# LilyPad-Dev-Simple-v12.net
KiCad netlist of a schematic drawn in EAGLE
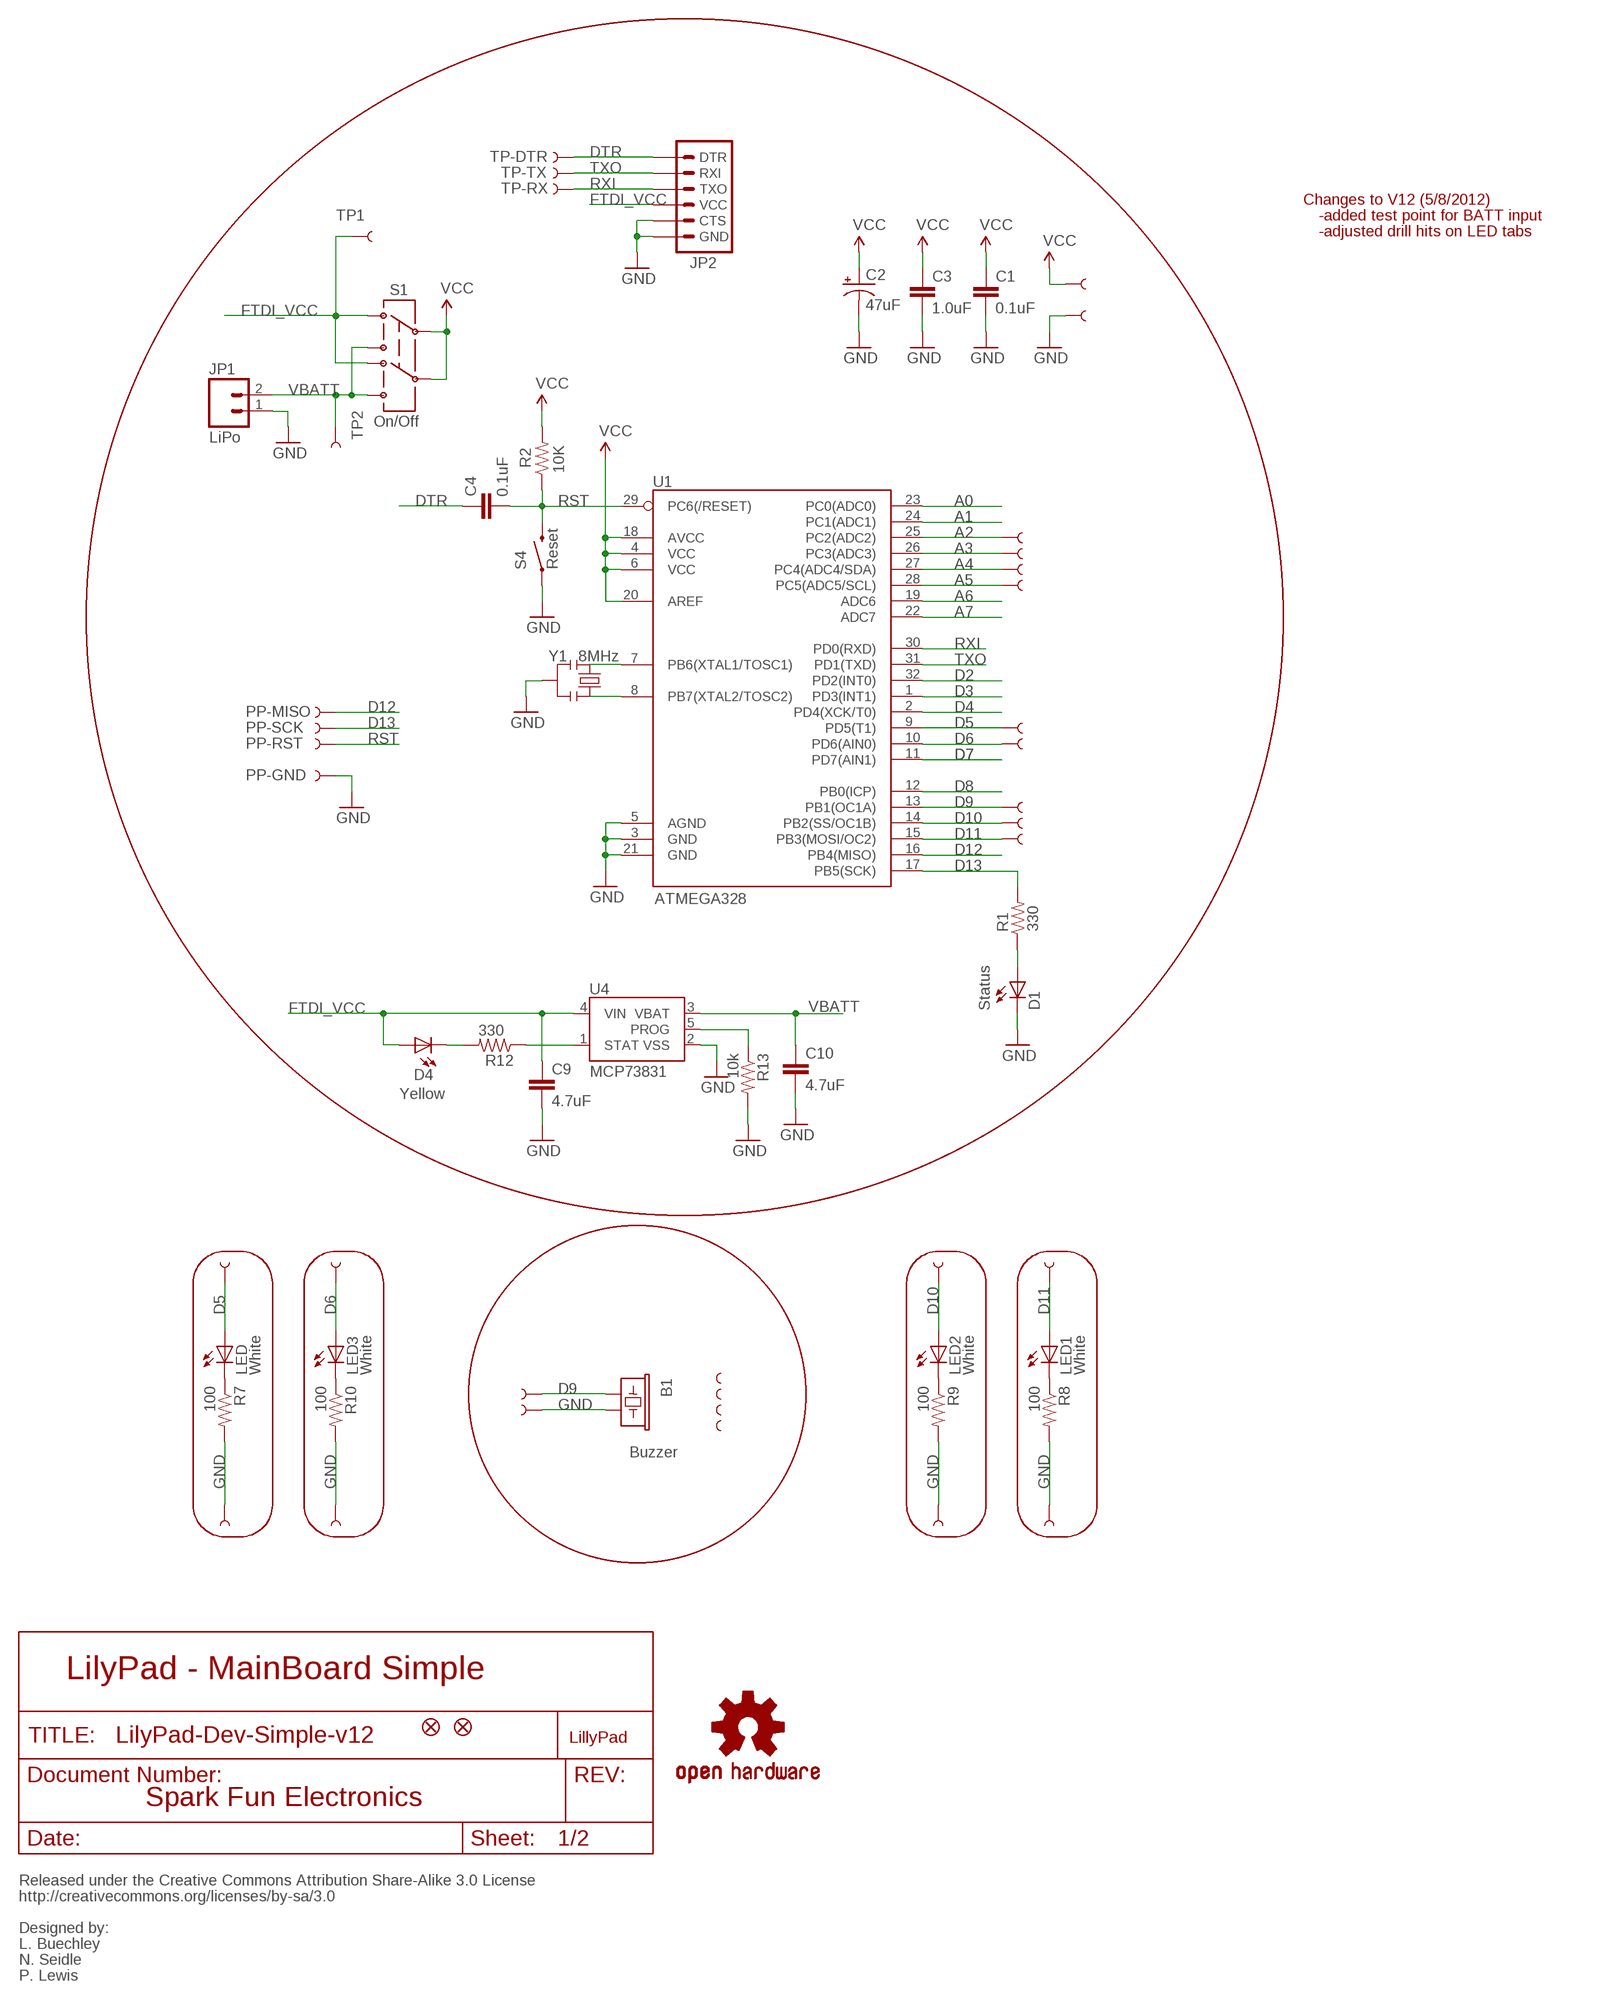
[diagram p0: schematic, sheet 1]

(export (version "E")
  (design (tool "Eeschema 10.0.6"))
  (components
    (comp (ref "1")
      (value "SEWTAP-NOHOLE2")
      (footprint "eagle-import:PETAL-NOHOLE-2SIDE")
      (libsource (lib "eagle-import") (part "SEWTAP-NOHOLE2"))
    )
    (comp (ref "2")
      (value "SEWTAP-NOHOLE2")
      (footprint "eagle-import:PETAL-NOHOLE-2SIDE")
      (libsource (lib "eagle-import") (part "SEWTAP-NOHOLE2"))
    )
    (comp (ref "3")
      (value "SEWTAP-NOHOLE2")
      (footprint "eagle-import:PETAL-NOHOLE-2SIDE")
      (libsource (lib "eagle-import") (part "SEWTAP-NOHOLE2"))
    )
    (comp (ref "4")
      (value "SEWTAP-NOHOLE2")
      (footprint "eagle-import:PETAL-NOHOLE-2SIDE")
      (libsource (lib "eagle-import") (part "SEWTAP-NOHOLE2"))
    )
    (comp (ref "A2/16")
      (value "SEWTAP9")
      (footprint "eagle-import:PETAL-LONG-1-2SIDE")
      (libsource (lib "eagle-import") (part "SEWTAP9"))
    )
    (comp (ref "A3/17")
      (value "SEWTAP9")
      (footprint "eagle-import:PETAL-LONG-1-2SIDE")
      (libsource (lib "eagle-import") (part "SEWTAP9"))
    )
    (comp (ref "A4/18")
      (value "SEWTAP9")
      (footprint "eagle-import:PETAL-LONG-1-2SIDE")
      (libsource (lib "eagle-import") (part "SEWTAP9"))
    )
    (comp (ref "A5/19")
      (value "SEWTAP9")
      (footprint "eagle-import:PETAL-LONG-1-2SIDE")
      (libsource (lib "eagle-import") (part "SEWTAP9"))
    )
    (comp (ref "B1")
      (value "Buzzer")
      (footprint "eagle-import:BUZZER-CCV")
      (libsource (lib "eagle-import") (part "BUZZERSMD2"))
    )
    (comp (ref "C1")
      (value "0.1uF")
      (footprint "eagle-import:0402-CAP")
      (libsource (lib "eagle-import") (part "CAP0402-CAP"))
    )
    (comp (ref "C2")
      (value "47uF")
      (footprint "eagle-import:EIA3528")
      (libsource (lib "eagle-import") (part "CAP_POL3528"))
    )
    (comp (ref "C3")
      (value "1.0uF")
      (footprint "eagle-import:0402-CAP")
      (libsource (lib "eagle-import") (part "CAP0402-CAP"))
    )
    (comp (ref "C4")
      (value "0.1uF")
      (footprint "eagle-import:0402-CAP")
      (libsource (lib "eagle-import") (part "CAP0402-CAP"))
    )
    (comp (ref "C9")
      (value "4.7uF")
      (footprint "eagle-import:0402-CAP")
      (libsource (lib "eagle-import") (part "CAP0402-CAP"))
    )
    (comp (ref "C10")
      (value "4.7uF")
      (footprint "eagle-import:0402-CAP")
      (libsource (lib "eagle-import") (part "CAP0402-CAP"))
    )
    (comp (ref "D1")
      (value "Status")
      (footprint "eagle-import:LED-0603")
      (libsource (lib "eagle-import") (part "LED0603"))
    )
    (comp (ref "D4")
      (value "Yellow")
      (footprint "eagle-import:LED-0603")
      (libsource (lib "eagle-import") (part "LED0603"))
    )
    (comp (ref "JP1")
      (value "LiPo")
      (footprint "eagle-import:JST-2-SMD")
      (libsource (lib "eagle-import") (part "M02-JST-2MM-SMT"))
    )
    (comp (ref "JP2")
      (value "ARDUINO_SERIAL_PROGRAMSMD")
      (footprint "eagle-import:1X06-SMD")
      (libsource (lib "eagle-import") (part "ARDUINO_SERIAL_PROGRAMSMD"))
    )
    (comp (ref "JP3")
      (value "FIDUCIAL1X2")
      (footprint "eagle-import:FIDUCIAL-1X2")
      (libsource (lib "eagle-import") (part "FIDUCIAL1X2"))
    )
    (comp (ref "JP4")
      (value "FIDUCIAL1X2")
      (footprint "eagle-import:FIDUCIAL-1X2")
      (libsource (lib "eagle-import") (part "FIDUCIAL1X2"))
    )
    (comp (ref "LED")
      (value "White")
      (footprint "eagle-import:LED-1206")
      (libsource (lib "eagle-import") (part "SparkFun-3-2-07_LED1206"))
    )
    (comp (ref "LED+")
      (value "SEWTAP6")
      (footprint "eagle-import:PETAL-SMALL-2SIDE")
      (libsource (lib "eagle-import") (part "SEWTAP6"))
    )
    (comp (ref "LED+1")
      (value "SEWTAP6")
      (footprint "eagle-import:PETAL-SMALL-2SIDE")
      (libsource (lib "eagle-import") (part "SEWTAP6"))
    )
    (comp (ref "LED+2")
      (value "SEWTAP6")
      (footprint "eagle-import:PETAL-SMALL-2SIDE")
      (libsource (lib "eagle-import") (part "SEWTAP6"))
    )
    (comp (ref "LED+3")
      (value "SEWTAP6")
      (footprint "eagle-import:PETAL-SMALL-2SIDE")
      (libsource (lib "eagle-import") (part "SEWTAP6"))
    )
    (comp (ref "LED-")
      (value "SEWTAP6")
      (footprint "eagle-import:PETAL-SMALL-2SIDE")
      (libsource (lib "eagle-import") (part "SEWTAP6"))
    )
    (comp (ref "LED-1")
      (value "SEWTAP6")
      (footprint "eagle-import:PETAL-SMALL-2SIDE")
      (libsource (lib "eagle-import") (part "SEWTAP6"))
    )
    (comp (ref "LED-2")
      (value "SEWTAP6")
      (footprint "eagle-import:PETAL-SMALL-2SIDE")
      (libsource (lib "eagle-import") (part "SEWTAP6"))
    )
    (comp (ref "LED-3")
      (value "SEWTAP6")
      (footprint "eagle-import:PETAL-SMALL-2SIDE")
      (libsource (lib "eagle-import") (part "SEWTAP6"))
    )
    (comp (ref "LED1")
      (value "White")
      (footprint "eagle-import:LED-1206")
      (libsource (lib "eagle-import") (part "SparkFun-3-2-07_LED1206"))
    )
    (comp (ref "LED2")
      (value "White")
      (footprint "eagle-import:LED-1206")
      (libsource (lib "eagle-import") (part "SparkFun-3-2-07_LED1206"))
    )
    (comp (ref "LED3")
      (value "White")
      (footprint "eagle-import:LED-1206")
      (libsource (lib "eagle-import") (part "SparkFun-3-2-07_LED1206"))
    )
    (comp (ref "LOGO")
      (value "LOGO-LPLPA")
      (footprint "eagle-import:LOGO-LPA")
      (libsource (lib "eagle-import") (part "LOGO-LPLPA"))
    )
    (comp (ref "PP-GND")
      (value "TEST-POINT3X5")
      (footprint "eagle-import:PAD.03X.05")
      (libsource (lib "eagle-import") (part "TEST-POINT3X5"))
    )
    (comp (ref "PP-MISO")
      (value "TEST-POINT3X5")
      (footprint "eagle-import:PAD.03X.05")
      (libsource (lib "eagle-import") (part "TEST-POINT3X5"))
    )
    (comp (ref "PP-RST")
      (value "TEST-POINT3X5")
      (footprint "eagle-import:PAD.03X.05")
      (libsource (lib "eagle-import") (part "TEST-POINT3X5"))
    )
    (comp (ref "PP-SCK")
      (value "TEST-POINT3X5")
      (footprint "eagle-import:PAD.03X.05")
      (libsource (lib "eagle-import") (part "TEST-POINT3X5"))
    )
    (comp (ref "R1")
      (value "330")
      (footprint "eagle-import:0402-RES")
      (libsource (lib "eagle-import") (part "RESISTOR0402-RES"))
    )
    (comp (ref "R2")
      (value "10K")
      (footprint "eagle-import:0402-RES")
      (libsource (lib "eagle-import") (part "RESISTOR0402-RES"))
    )
    (comp (ref "R7")
      (value "100")
      (footprint "eagle-import:0603-RES")
      (libsource (lib "eagle-import") (part "RESISTOR0603-RES"))
    )
    (comp (ref "R8")
      (value "100")
      (footprint "eagle-import:0603-RES")
      (libsource (lib "eagle-import") (part "RESISTOR0603-RES"))
    )
    (comp (ref "R9")
      (value "100")
      (footprint "eagle-import:0603-RES")
      (libsource (lib "eagle-import") (part "RESISTOR0603-RES"))
    )
    (comp (ref "R10")
      (value "100")
      (footprint "eagle-import:0603-RES")
      (libsource (lib "eagle-import") (part "RESISTOR0603-RES"))
    )
    (comp (ref "R12")
      (value "330")
      (footprint "eagle-import:0402-RES")
      (libsource (lib "eagle-import") (part "RESISTOR0402-RES"))
    )
    (comp (ref "R13")
      (value "10k")
      (footprint "eagle-import:0402-RES")
      (libsource (lib "eagle-import") (part "RESISTOR0402-RES"))
    )
    (comp (ref "S1")
      (value "On/Off")
      (footprint "eagle-import:AYZ0202")
      (libsource (lib "eagle-import") (part "AYZ0202"))
    )
    (comp (ref "S4")
      (value "Reset")
      (footprint "eagle-import:TACTILE_SWITCH_SMD")
      (libsource (lib "eagle-import") (part "SWITCH-MOMENTARY-2SMD"))
    )
    (comp (ref "TP-DTR")
      (value "TEST-POINT3X5")
      (footprint "eagle-import:PAD.03X.05")
      (libsource (lib "eagle-import") (part "TEST-POINT3X5"))
    )
    (comp (ref "TP-RX")
      (value "TEST-POINT3X5")
      (footprint "eagle-import:PAD.03X.05")
      (libsource (lib "eagle-import") (part "TEST-POINT3X5"))
    )
    (comp (ref "TP-TX")
      (value "TEST-POINT3X5")
      (footprint "eagle-import:PAD.03X.05")
      (libsource (lib "eagle-import") (part "TEST-POINT3X5"))
    )
    (comp (ref "TP1")
      (value "TEST-POINT3X5")
      (footprint "eagle-import:PAD.03X.05")
      (libsource (lib "eagle-import") (part "TEST-POINT3X5"))
    )
    (comp (ref "TP2")
      (value "TEST-POINT3X5")
      (footprint "eagle-import:PAD.03X.05")
      (libsource (lib "eagle-import") (part "TEST-POINT3X5"))
    )
    (comp (ref "U$1")
      (value "SEWTAP9")
      (footprint "eagle-import:PETAL-LONG-1-2SIDE")
      (libsource (lib "eagle-import") (part "SEWTAP9"))
    )
    (comp (ref "U$2")
      (value "OSHW-LOGOS")
      (footprint "eagle-import:OSHW-LOGO-S")
      (libsource (lib "eagle-import") (part "OSHW-LOGOS"))
    )
    (comp (ref "U$4")
      (value "SEWTAP9")
      (footprint "eagle-import:PETAL-LONG-1-2SIDE")
      (libsource (lib "eagle-import") (part "SEWTAP9"))
    )
    (comp (ref "U$32-")
      (value "SEWTAP6")
      (footprint "eagle-import:PETAL-SMALL")
      (libsource (lib "eagle-import") (part "SEWTAP4"))
    )
    (comp (ref "U$33+")
      (value "SEWTAP6")
      (footprint "eagle-import:PETAL-SMALL")
      (libsource (lib "eagle-import") (part "SEWTAP4"))
    )
    (comp (ref "U$37")
      (value "SEWTAP9")
      (footprint "eagle-import:PETAL-LONG-1-2SIDE")
      (libsource (lib "eagle-import") (part "SEWTAP9"))
    )
    (comp (ref "U$39")
      (value "SEWTAP9")
      (footprint "eagle-import:PETAL-LONG-1-2SIDE")
      (libsource (lib "eagle-import") (part "SEWTAP9"))
    )
    (comp (ref "U$41")
      (value "SEWTAP9")
      (footprint "eagle-import:PETAL-LONG-1-2SIDE")
      (libsource (lib "eagle-import") (part "SEWTAP9"))
    )
    (comp (ref "U$43")
      (value "SEWTAP9")
      (footprint "eagle-import:PETAL-LONG-1-2SIDE")
      (libsource (lib "eagle-import") (part "SEWTAP9"))
    )
    (comp (ref "U$45")
      (value "SEWTAP9")
      (footprint "eagle-import:PETAL-LONG-1-2SIDE")
      (libsource (lib "eagle-import") (part "SEWTAP9"))
    )
    (comp (ref "U1")
      (value "ATMEGA328")
      (footprint "eagle-import:TQFP32-08")
      (libsource (lib "eagle-import") (part "ATMEGA168"))
    )
    (comp (ref "U4")
      (value "MCP73831")
      (footprint "eagle-import:SOT23-5")
      (libsource (lib "eagle-import") (part "MCP73831"))
    )
    (comp (ref "Y1")
      (value "8MHz")
      (footprint "eagle-import:RESONATOR-SMD")
      (libsource (lib "eagle-import") (part "RESONATORSMD"))
    )
  )
  (nets
    (net (code "1") (name "A0") (class "Default")
      (node (ref "U1") (pin "23") (pinfunction "PC0(ADC0)_23") (pintype "bidirectional"))
    )
    (net (code "2") (name "A1") (class "Default")
      (node (ref "U1") (pin "24") (pinfunction "PC1(ADC1)_24") (pintype "bidirectional"))
    )
    (net (code "3") (name "A2") (class "Default")
      (node (ref "A2/16") (pin "1") (pinfunction "1_1") (pintype "bidirectional"))
      (node (ref "U1") (pin "25") (pinfunction "PC2(ADC2)_25") (pintype "bidirectional"))
    )
    (net (code "4") (name "A3") (class "Default")
      (node (ref "A3/17") (pin "1") (pinfunction "1_1") (pintype "bidirectional"))
      (node (ref "U1") (pin "26") (pinfunction "PC3(ADC3)_26") (pintype "bidirectional"))
    )
    (net (code "5") (name "A4") (class "Default")
      (node (ref "A4/18") (pin "1") (pinfunction "1_1") (pintype "bidirectional"))
      (node (ref "U1") (pin "27") (pinfunction "PC4(ADC4/SDA)_27") (pintype "bidirectional"))
    )
    (net (code "6") (name "A5") (class "Default")
      (node (ref "A5/19") (pin "1") (pinfunction "1_1") (pintype "bidirectional"))
      (node (ref "U1") (pin "28") (pinfunction "PC5(ADC5/SCL)_28") (pintype "bidirectional"))
    )
    (net (code "7") (name "A6") (class "Default")
      (node (ref "U1") (pin "19") (pinfunction "ADC6_19") (pintype "bidirectional"))
    )
    (net (code "8") (name "A7") (class "Default")
      (node (ref "U1") (pin "22") (pinfunction "ADC7_22") (pintype "bidirectional"))
    )
    (net (code "9") (name "D2") (class "Default")
      (node (ref "U1") (pin "32") (pinfunction "PD2(INT0)_32") (pintype "bidirectional"))
    )
    (net (code "10") (name "D3") (class "Default")
      (node (ref "U1") (pin "1") (pinfunction "PD3(INT1)_1") (pintype "bidirectional"))
    )
    (net (code "11") (name "D4") (class "Default")
      (node (ref "U1") (pin "2") (pinfunction "PD4(XCK/T0)_2") (pintype "bidirectional"))
    )
    (net (code "12") (name "D5") (class "Default")
      (node (ref "LED") (pin "A") (pinfunction "A_A") (pintype "passive"))
      (node (ref "LED+") (pin "1") (pinfunction "1_1") (pintype "bidirectional"))
      (node (ref "U$41") (pin "1") (pinfunction "1_1") (pintype "bidirectional"))
      (node (ref "U1") (pin "9") (pinfunction "PD5(T1)_9") (pintype "bidirectional"))
    )
    (net (code "13") (name "D6") (class "Default")
      (node (ref "LED+3") (pin "1") (pinfunction "1_1") (pintype "bidirectional"))
      (node (ref "LED3") (pin "A") (pinfunction "A_A") (pintype "passive"))
      (node (ref "U$1") (pin "1") (pinfunction "1_1") (pintype "bidirectional"))
      (node (ref "U1") (pin "10") (pinfunction "PD6(AIN0)_10") (pintype "bidirectional"))
    )
    (net (code "14") (name "D7") (class "Default")
      (node (ref "U1") (pin "11") (pinfunction "PD7(AIN1)_11") (pintype "bidirectional"))
    )
    (net (code "15") (name "D8") (class "Default")
      (node (ref "U1") (pin "12") (pinfunction "PB0(ICP)_12") (pintype "bidirectional"))
    )
    (net (code "16") (name "D9") (class "Default")
      (node (ref "B1") (pin "+") (pinfunction "1_+") (pintype "passive"))
      (node (ref "U$33+") (pin "1") (pinfunction "1_1") (pintype "bidirectional"))
      (node (ref "U$37") (pin "1") (pinfunction "1_1") (pintype "bidirectional"))
      (node (ref "U1") (pin "13") (pinfunction "PB1(OC1A)_13") (pintype "bidirectional"))
    )
    (net (code "17") (name "D10") (class "Default")
      (node (ref "LED+2") (pin "1") (pinfunction "1_1") (pintype "bidirectional"))
      (node (ref "LED2") (pin "A") (pinfunction "A_A") (pintype "passive"))
      (node (ref "U$39") (pin "1") (pinfunction "1_1") (pintype "bidirectional"))
      (node (ref "U1") (pin "14") (pinfunction "PB2(SS/OC1B)_14") (pintype "bidirectional"))
    )
    (net (code "18") (name "D11") (class "Default")
      (node (ref "LED+1") (pin "1") (pinfunction "1_1") (pintype "bidirectional"))
      (node (ref "LED1") (pin "A") (pinfunction "A_A") (pintype "passive"))
      (node (ref "U$4") (pin "1") (pinfunction "1_1") (pintype "bidirectional"))
      (node (ref "U1") (pin "15") (pinfunction "PB3(MOSI/OC2)_15") (pintype "bidirectional"))
    )
    (net (code "19") (name "D12") (class "Default")
      (node (ref "PP-MISO") (pin "P$1") (pinfunction "1_P$1") (pintype "bidirectional"))
      (node (ref "U1") (pin "16") (pinfunction "PB4(MISO)_16") (pintype "bidirectional"))
    )
    (net (code "20") (name "D13") (class "Default")
      (node (ref "PP-SCK") (pin "P$1") (pinfunction "1_P$1") (pintype "bidirectional"))
      (node (ref "R1") (pin "2") (pinfunction "2_2") (pintype "passive"))
      (node (ref "U1") (pin "17") (pinfunction "PB5(SCK)_17") (pintype "bidirectional"))
    )
    (net (code "21") (name "DTR") (class "Default")
      (node (ref "C4") (pin "1") (pinfunction "1_1") (pintype "passive"))
      (node (ref "JP2") (pin "1") (pinfunction "DTR_1") (pintype "passive"))
      (node (ref "TP-DTR") (pin "P$1") (pinfunction "1_P$1") (pintype "bidirectional"))
    )
    (net (code "22") (name "FTDI_VCC") (class "Default")
      (node (ref "C9") (pin "1") (pinfunction "1_1") (pintype "passive"))
      (node (ref "D4") (pin "A") (pinfunction "A_A") (pintype "passive"))
      (node (ref "JP2") (pin "4") (pinfunction "VCC_4") (pintype "passive"))
      (node (ref "S1") (pin "3") (pinfunction "1_3") (pintype "bidirectional"))
      (node (ref "S1") (pin "6") (pinfunction "4_6") (pintype "bidirectional"))
      (node (ref "TP1") (pin "P$1") (pinfunction "1_P$1") (pintype "bidirectional"))
      (node (ref "U4") (pin "4") (pinfunction "VIN_4") (pintype "power_in"))
    )
    (net (code "23") (name "GND") (class "Default")
      (node (ref "B1") (pin "-") (pinfunction "2_-") (pintype "passive"))
      (node (ref "C1") (pin "2") (pinfunction "2_2") (pintype "passive"))
      (node (ref "C10") (pin "2") (pinfunction "2_2") (pintype "passive"))
      (node (ref "C2") (pin "C") (pinfunction "-_C") (pintype "passive"))
      (node (ref "C3") (pin "2") (pinfunction "2_2") (pintype "passive"))
      (node (ref "C9") (pin "2") (pinfunction "2_2") (pintype "passive"))
      (node (ref "D1") (pin "C") (pinfunction "C_C") (pintype "passive"))
      (node (ref "JP1") (pin "1") (pinfunction "1_1") (pintype "passive"))
      (node (ref "JP2") (pin "5") (pinfunction "CTS_5") (pintype "passive"))
      (node (ref "JP2") (pin "6") (pinfunction "GND_6") (pintype "passive"))
      (node (ref "LED-") (pin "1") (pinfunction "1_1") (pintype "bidirectional"))
      (node (ref "LED-1") (pin "1") (pinfunction "1_1") (pintype "bidirectional"))
      (node (ref "LED-2") (pin "1") (pinfunction "1_1") (pintype "bidirectional"))
      (node (ref "LED-3") (pin "1") (pinfunction "1_1") (pintype "bidirectional"))
      (node (ref "PP-GND") (pin "P$1") (pinfunction "1_P$1") (pintype "bidirectional"))
      (node (ref "R10") (pin "2") (pinfunction "2_2") (pintype "passive"))
      (node (ref "R13") (pin "2") (pinfunction "2_2") (pintype "passive"))
      (node (ref "R7") (pin "2") (pinfunction "2_2") (pintype "passive"))
      (node (ref "R8") (pin "2") (pinfunction "2_2") (pintype "passive"))
      (node (ref "R9") (pin "2") (pinfunction "2_2") (pintype "passive"))
      (node (ref "S4") (pin "1") (pinfunction "1_1") (pintype "passive"))
      (node (ref "U$32-") (pin "1") (pinfunction "1_1") (pintype "bidirectional"))
      (node (ref "U$43") (pin "1") (pinfunction "1_1") (pintype "bidirectional"))
      (node (ref "U1") (pin "21") (pinfunction "GND_21") (pintype "bidirectional"))
      (node (ref "U1") (pin "3") (pinfunction "GND_3") (pintype "bidirectional"))
      (node (ref "U1") (pin "5") (pinfunction "AGND_5") (pintype "bidirectional"))
      (node (ref "U4") (pin "2") (pinfunction "VSS_2") (pintype "power_in"))
      (node (ref "Y1") (pin "2") (pinfunction "2_2") (pintype "passive"))
    )
    (net (code "24") (name "Net-(D1-PadA)") (class "Default")
      (node (ref "D1") (pin "A") (pinfunction "A_A") (pintype "passive"))
      (node (ref "R1") (pin "1") (pinfunction "1_1") (pintype "passive"))
    )
    (net (code "25") (name "Net-(D4-PadC)") (class "Default")
      (node (ref "D4") (pin "C") (pinfunction "C_C") (pintype "passive"))
      (node (ref "R12") (pin "2") (pinfunction "2_2") (pintype "passive"))
    )
    (net (code "26") (name "Net-(LED-PadC)") (class "Default")
      (node (ref "LED") (pin "C") (pinfunction "C_C") (pintype "passive"))
      (node (ref "R7") (pin "1") (pinfunction "1_1") (pintype "passive"))
    )
    (net (code "27") (name "Net-(LED1-PadC)") (class "Default")
      (node (ref "LED1") (pin "C") (pinfunction "C_C") (pintype "passive"))
      (node (ref "R8") (pin "1") (pinfunction "1_1") (pintype "passive"))
    )
    (net (code "28") (name "Net-(LED2-PadC)") (class "Default")
      (node (ref "LED2") (pin "C") (pinfunction "C_C") (pintype "passive"))
      (node (ref "R9") (pin "1") (pinfunction "1_1") (pintype "passive"))
    )
    (net (code "29") (name "Net-(LED3-PadC)") (class "Default")
      (node (ref "LED3") (pin "C") (pinfunction "C_C") (pintype "passive"))
      (node (ref "R10") (pin "1") (pinfunction "1_1") (pintype "passive"))
    )
    (net (code "30") (name "Net-(U1-PB6(XTAL1{slash}TOSC1))") (class "Default")
      (node (ref "U1") (pin "7") (pinfunction "PB6(XTAL1/TOSC1)_7") (pintype "bidirectional"))
      (node (ref "Y1") (pin "1") (pinfunction "1_1") (pintype "passive"))
    )
    (net (code "31") (name "Net-(U1-PB7(XTAL2{slash}TOSC2))") (class "Default")
      (node (ref "U1") (pin "8") (pinfunction "PB7(XTAL2/TOSC2)_8") (pintype "bidirectional"))
      (node (ref "Y1") (pin "3") (pinfunction "3_3") (pintype "passive"))
    )
    (net (code "32") (name "Net-(U4-PROG)") (class "Default")
      (node (ref "R13") (pin "1") (pinfunction "1_1") (pintype "passive"))
      (node (ref "U4") (pin "5") (pinfunction "PROG_5") (pintype "input"))
    )
    (net (code "33") (name "Net-(U4-STAT)") (class "Default")
      (node (ref "R12") (pin "1") (pinfunction "1_1") (pintype "passive"))
      (node (ref "U4") (pin "1") (pinfunction "STAT_1") (pintype "output"))
    )
    (net (code "34") (name "RST") (class "Default")
      (node (ref "C4") (pin "2") (pinfunction "2_2") (pintype "passive"))
      (node (ref "PP-RST") (pin "P$1") (pinfunction "1_P$1") (pintype "bidirectional"))
      (node (ref "R2") (pin "1") (pinfunction "1_1") (pintype "passive"))
      (node (ref "S4") (pin "3") (pinfunction "2_3") (pintype "passive"))
      (node (ref "U1") (pin "29") (pinfunction "PC6(/RESET)_29") (pintype "bidirectional"))
    )
    (net (code "35") (name "RXI") (class "Default")
      (node (ref "JP2") (pin "3") (pinfunction "TXO_3") (pintype "passive"))
      (node (ref "TP-RX") (pin "P$1") (pinfunction "1_P$1") (pintype "bidirectional"))
      (node (ref "U1") (pin "30") (pinfunction "PD0(RXD)_30") (pintype "bidirectional"))
    )
    (net (code "36") (name "TXO") (class "Default")
      (node (ref "JP2") (pin "2") (pinfunction "RXI_2") (pintype "passive"))
      (node (ref "TP-TX") (pin "P$1") (pinfunction "1_P$1") (pintype "bidirectional"))
      (node (ref "U1") (pin "31") (pinfunction "PD1(TXD)_31") (pintype "bidirectional"))
    )
    (net (code "37") (name "VBATT") (class "Default")
      (node (ref "C10") (pin "1") (pinfunction "1_1") (pintype "passive"))
      (node (ref "JP1") (pin "2") (pinfunction "2_2") (pintype "passive"))
      (node (ref "S1") (pin "1") (pinfunction "3_1") (pintype "bidirectional"))
      (node (ref "S1") (pin "4") (pinfunction "6_4") (pintype "bidirectional"))
      (node (ref "TP2") (pin "P$1") (pinfunction "1_P$1") (pintype "bidirectional"))
      (node (ref "U4") (pin "3") (pinfunction "VBAT_3") (pintype "power_in"))
    )
    (net (code "38") (name "VCC") (class "Default")
      (node (ref "C1") (pin "1") (pinfunction "1_1") (pintype "passive"))
      (node (ref "C2") (pin "A") (pinfunction "+_A") (pintype "passive"))
      (node (ref "C3") (pin "1") (pinfunction "1_1") (pintype "passive"))
      (node (ref "R2") (pin "2") (pinfunction "2_2") (pintype "passive"))
      (node (ref "S1") (pin "2") (pinfunction "2_2") (pintype "bidirectional"))
      (node (ref "S1") (pin "5") (pinfunction "5_5") (pintype "bidirectional"))
      (node (ref "U$45") (pin "1") (pinfunction "1_1") (pintype "bidirectional"))
      (node (ref "U1") (pin "18") (pinfunction "AVCC_18") (pintype "bidirectional"))
      (node (ref "U1") (pin "20") (pinfunction "AREF_20") (pintype "bidirectional"))
      (node (ref "U1") (pin "4") (pinfunction "VCC_4") (pintype "bidirectional"))
      (node (ref "U1") (pin "6") (pinfunction "VCC_6") (pintype "bidirectional"))
    )
  )
)
